# M410A.net
KiCad netlist of a schematic drawn in EAGLE
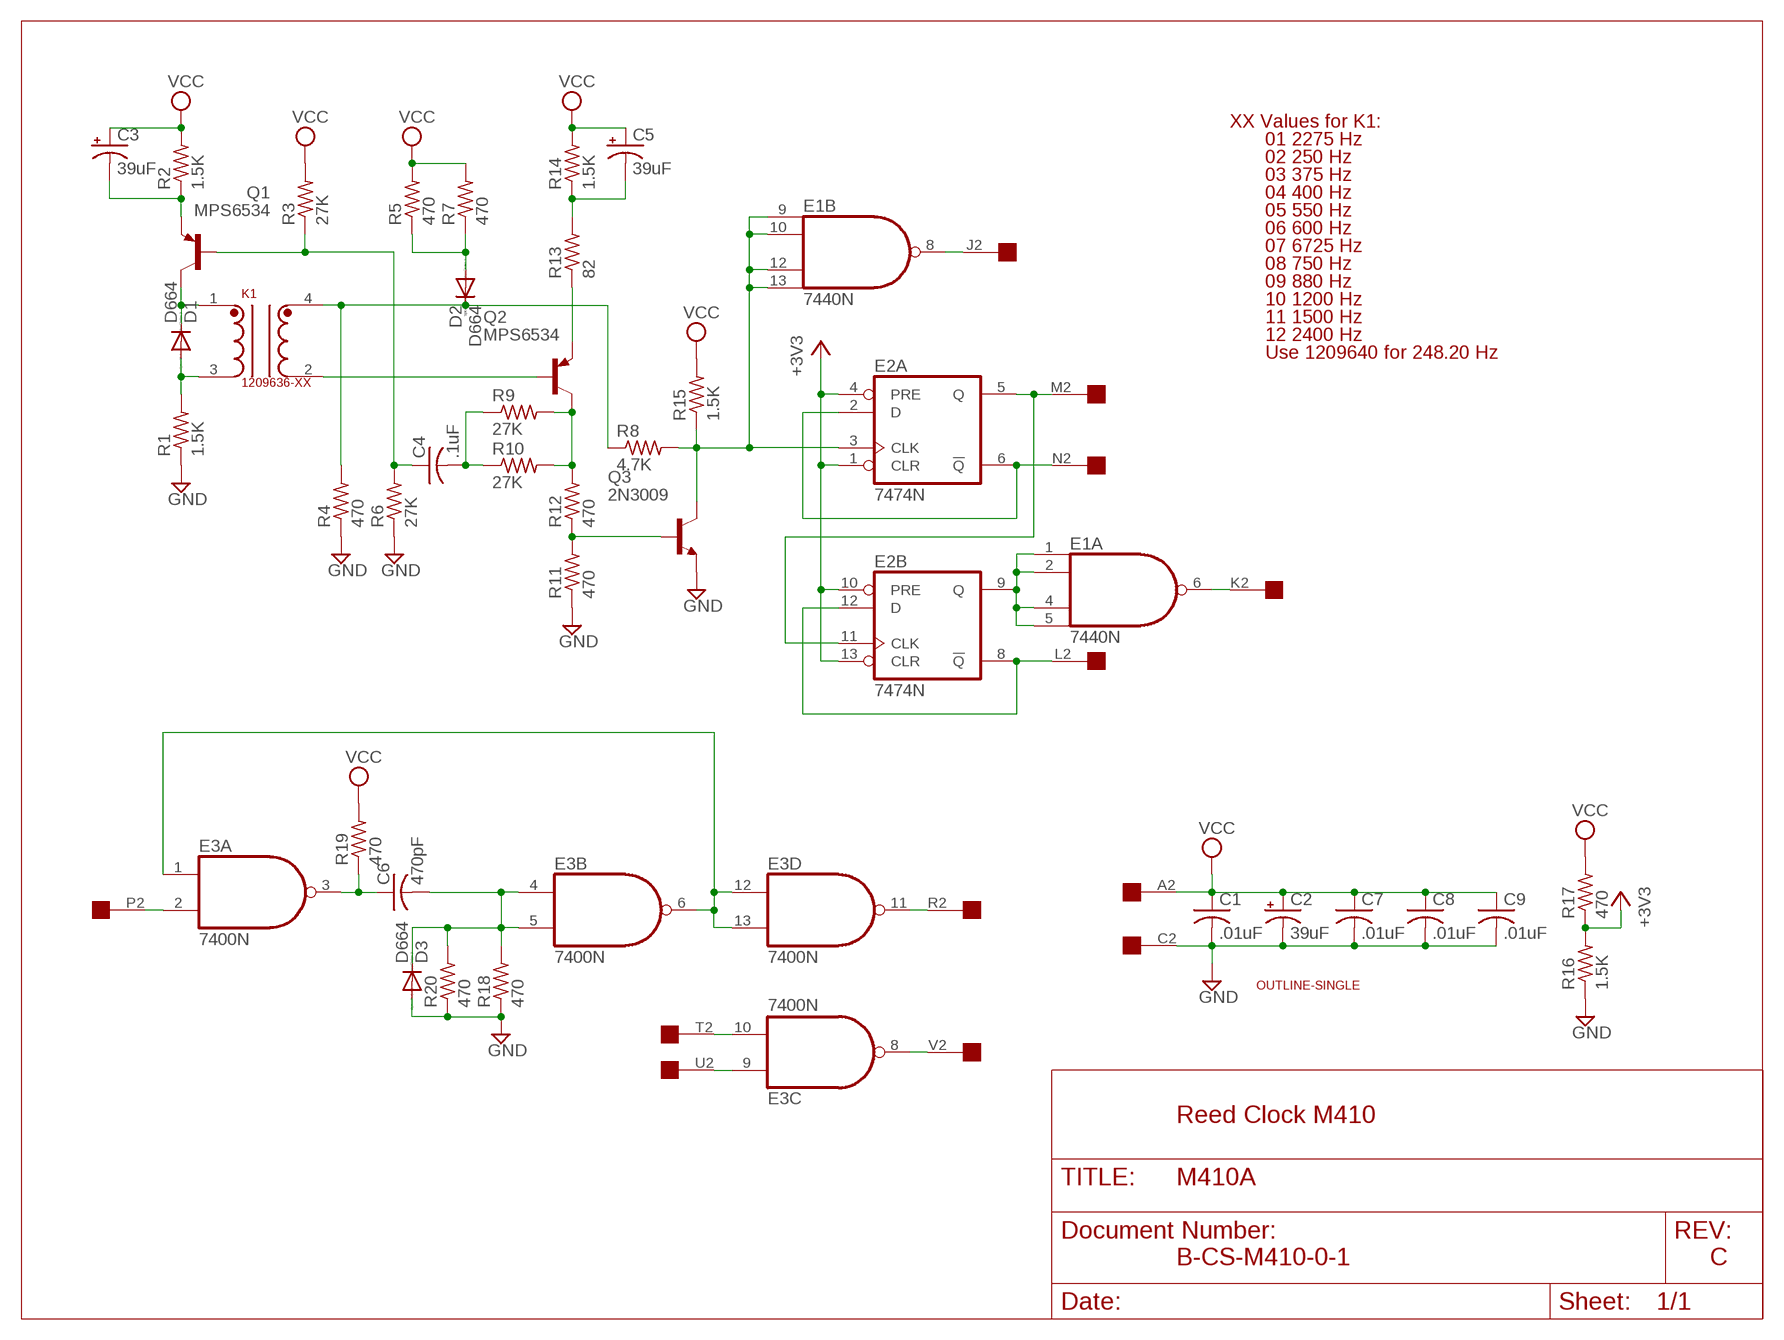
[diagram p0: schematic, sheet 1]

(export (version "E")
  (design (tool "Eeschema 10.0.6"))
  (components
    (comp (ref "C1")
      (value ".01uF")
      (footprint "eagle-import:C050-025X075")
      (libsource (lib "eagle-import") (part "C-US050-025X075"))
    )
    (comp (ref "C2")
      (value "39uF")
      (footprint "eagle-import:E12-8")
      (libsource (lib "eagle-import") (part "CPOL-USE20-8AXIAL"))
    )
    (comp (ref "C3")
      (value "39uF")
      (footprint "eagle-import:E12-8")
      (libsource (lib "eagle-import") (part "CPOL-USE20-8AXIAL"))
    )
    (comp (ref "C4")
      (value ".1uF")
      (footprint "eagle-import:C150-054X183")
      (libsource (lib "eagle-import") (part "C-US150-054X183"))
    )
    (comp (ref "C5")
      (value "39uF")
      (footprint "eagle-import:E12-8")
      (libsource (lib "eagle-import") (part "CPOL-USE20-8AXIAL"))
    )
    (comp (ref "C6")
      (value "470pF")
      (footprint "eagle-import:C075-032X103")
      (libsource (lib "eagle-import") (part "C-US075-032X103"))
    )
    (comp (ref "C7")
      (value ".01uF")
      (footprint "eagle-import:C050-025X075")
      (libsource (lib "eagle-import") (part "C-US050-025X075"))
    )
    (comp (ref "C8")
      (value ".01uF")
      (footprint "eagle-import:C050-025X075")
      (libsource (lib "eagle-import") (part "C-US050-025X075"))
    )
    (comp (ref "C9")
      (value ".01uF")
      (footprint "eagle-import:C050-025X075")
      (libsource (lib "eagle-import") (part "C-US050-025X075"))
    )
    (comp (ref "D1")
      (value "D664")
      (footprint "eagle-import:DO35-10")
      (libsource (lib "eagle-import") (part "DIODE-DO35-10"))
    )
    (comp (ref "D2")
      (value "D664")
      (footprint "eagle-import:DO35-10")
      (libsource (lib "eagle-import") (part "DIODE-DO35-10"))
    )
    (comp (ref "D3")
      (value "D664")
      (footprint "eagle-import:DO35-10")
      (libsource (lib "eagle-import") (part "DIODE-DO35-10"))
    )
    (comp (ref "E1")
      (value "7440N")
      (footprint "eagle-import:DIL14")
      (libsource (lib "eagle-import") (part "7440N"))
    )
    (comp (ref "E2")
      (value "7474N")
      (footprint "eagle-import:DIL14")
      (libsource (lib "eagle-import") (part "7474NS"))
    )
    (comp (ref "E3")
      (value "7400N")
      (footprint "eagle-import:DIL14")
      (libsource (lib "eagle-import") (part "7400N"))
    )
    (comp (ref "K1")
      (value "1209636-XX")
      (footprint "eagle-import:RESONATOR")
      (libsource (lib "eagle-import") (part "RESONATOR"))
    )
    (comp (ref "Q1")
      (value "MPS6534")
      (footprint "eagle-import:TO5")
      (libsource (lib "eagle-import") (part "-PNP-TO5"))
    )
    (comp (ref "Q2")
      (value "MPS6534")
      (footprint "eagle-import:TO5")
      (libsource (lib "eagle-import") (part "-PNP-TO5"))
    )
    (comp (ref "Q3")
      (value "2N3009")
      (footprint "eagle-import:TO5")
      (libsource (lib "eagle-import") (part "-NPN-TO5"))
    )
    (comp (ref "R1")
      (value "1.5K")
      (footprint "eagle-import:0207_10")
      (libsource (lib "eagle-import") (part "R-US_0207/10"))
    )
    (comp (ref "R2")
      (value "1.5K")
      (footprint "eagle-import:0207_10")
      (libsource (lib "eagle-import") (part "R-US_0207/10"))
    )
    (comp (ref "R3")
      (value "27K")
      (footprint "eagle-import:0207_10")
      (libsource (lib "eagle-import") (part "R-US_0207/10"))
    )
    (comp (ref "R4")
      (value "470")
      (footprint "eagle-import:0207_10")
      (libsource (lib "eagle-import") (part "R-US_0207/10"))
    )
    (comp (ref "R5")
      (value "470")
      (footprint "eagle-import:0207_10")
      (libsource (lib "eagle-import") (part "R-US_0207/10"))
    )
    (comp (ref "R6")
      (value "27K")
      (footprint "eagle-import:0207_10")
      (libsource (lib "eagle-import") (part "R-US_0207/10"))
    )
    (comp (ref "R7")
      (value "470")
      (footprint "eagle-import:0207_10")
      (libsource (lib "eagle-import") (part "R-US_0207/10"))
    )
    (comp (ref "R8")
      (value "4.7K")
      (footprint "eagle-import:0207_10")
      (libsource (lib "eagle-import") (part "R-US_0207/10"))
    )
    (comp (ref "R9")
      (value "27K")
      (footprint "eagle-import:0207_10")
      (libsource (lib "eagle-import") (part "R-US_0207/10"))
    )
    (comp (ref "R10")
      (value "27K")
      (footprint "eagle-import:0207_10")
      (libsource (lib "eagle-import") (part "R-US_0207/10"))
    )
    (comp (ref "R11")
      (value "470")
      (footprint "eagle-import:0207_10")
      (libsource (lib "eagle-import") (part "R-US_0207/10"))
    )
    (comp (ref "R12")
      (value "470")
      (footprint "eagle-import:0207_10")
      (libsource (lib "eagle-import") (part "R-US_0207/10"))
    )
    (comp (ref "R13")
      (value "82")
      (footprint "eagle-import:0207_10")
      (libsource (lib "eagle-import") (part "R-US_0207/10"))
    )
    (comp (ref "R14")
      (value "1.5K")
      (footprint "eagle-import:0207_10")
      (libsource (lib "eagle-import") (part "R-US_0207/10"))
    )
    (comp (ref "R15")
      (value "1.5K")
      (footprint "eagle-import:0207_10")
      (libsource (lib "eagle-import") (part "R-US_0207/10"))
    )
    (comp (ref "R16")
      (value "1.5K")
      (footprint "eagle-import:0207_10")
      (libsource (lib "eagle-import") (part "R-US_0207/10"))
    )
    (comp (ref "R17")
      (value "470")
      (footprint "eagle-import:0207_10")
      (libsource (lib "eagle-import") (part "R-US_0207/10"))
    )
    (comp (ref "R18")
      (value "470")
      (footprint "eagle-import:0207_10")
      (libsource (lib "eagle-import") (part "R-US_0207/10"))
    )
    (comp (ref "R19")
      (value "470")
      (footprint "eagle-import:0207_10")
      (libsource (lib "eagle-import") (part "R-US_0207/10"))
    )
    (comp (ref "R20")
      (value "470")
      (footprint "eagle-import:0207_10")
      (libsource (lib "eagle-import") (part "R-US_0207/10"))
    )
    (comp (ref "U$1")
      (value "OUTLINE-SINGLE")
      (footprint "eagle-import:SINGLE")
      (libsource (lib "eagle-import") (part "OUTLINE-SINGLE"))
    )
    (comp (ref "U$3")
      (value "EDGE-1")
      (footprint "eagle-import:EDGE-CON1")
      (libsource (lib "eagle-import") (part "EDGE-1"))
    )
  )
  (nets
    (net (code "1") (name "+3V3") (class "Default")
      (node (ref "E2") (pin "1") (pinfunction "CLR_1") (pintype "input"))
      (node (ref "E2") (pin "10") (pinfunction "PRE_10") (pintype "input"))
      (node (ref "E2") (pin "13") (pinfunction "CLR_13") (pintype "input"))
      (node (ref "E2") (pin "4") (pinfunction "PRE_4") (pintype "input"))
      (node (ref "R16") (pin "2") (pinfunction "2_2") (pintype "passive"))
      (node (ref "R17") (pin "1") (pinfunction "1_1") (pintype "passive"))
    )
    (net (code "2") (name "GND") (class "Default")
      (node (ref "C1") (pin "2") (pinfunction "2_2") (pintype "passive"))
      (node (ref "C2") (pin "-") (pinfunction "-_-") (pintype "passive"))
      (node (ref "C7") (pin "2") (pinfunction "2_2") (pintype "passive"))
      (node (ref "C8") (pin "2") (pinfunction "2_2") (pintype "passive"))
      (node (ref "C9") (pin "2") (pinfunction "2_2") (pintype "passive"))
      (node (ref "D3") (pin "A") (pinfunction "A_A") (pintype "passive"))
      (node (ref "Q3") (pin "1") (pinfunction "E_1") (pintype "passive"))
      (node (ref "R1") (pin "1") (pinfunction "1_1") (pintype "passive"))
      (node (ref "R11") (pin "1") (pinfunction "1_1") (pintype "passive"))
      (node (ref "R16") (pin "1") (pinfunction "1_1") (pintype "passive"))
      (node (ref "R18") (pin "1") (pinfunction "1_1") (pintype "passive"))
      (node (ref "R20") (pin "1") (pinfunction "1_1") (pintype "passive"))
      (node (ref "R4") (pin "1") (pinfunction "1_1") (pintype "passive"))
      (node (ref "R6") (pin "1") (pinfunction "1_1") (pintype "passive"))
      (node (ref "U$3") (pin "C2") (pinfunction "1_C2") (pintype "bidirectional"))
    )
    (net (code "3") (name "Net-(C4-Pad2)") (class "Default")
      (node (ref "C4") (pin "2") (pinfunction "2_2") (pintype "passive"))
      (node (ref "R10") (pin "1") (pinfunction "1_1") (pintype "passive"))
      (node (ref "R9") (pin "1") (pinfunction "1_1") (pintype "passive"))
    )
    (net (code "4") (name "Net-(C5-Pad-)") (class "Default")
      (node (ref "C5") (pin "-") (pinfunction "-_-") (pintype "passive"))
      (node (ref "R13") (pin "2") (pinfunction "2_2") (pintype "passive"))
      (node (ref "R14") (pin "1") (pinfunction "1_1") (pintype "passive"))
    )
    (net (code "5") (name "Net-(D2-PadA)") (class "Default")
      (node (ref "D2") (pin "A") (pinfunction "A_A") (pintype "passive"))
      (node (ref "R5") (pin "1") (pinfunction "1_1") (pintype "passive"))
      (node (ref "R7") (pin "1") (pinfunction "1_1") (pintype "passive"))
    )
    (net (code "6") (name "Net-(E1C-I0)") (class "Default")
      (node (ref "E1") (pin "1") (pinfunction "I0_1") (pintype "input"))
      (node (ref "E1") (pin "2") (pinfunction "I1_2") (pintype "input"))
      (node (ref "E1") (pin "4") (pinfunction "I2_4") (pintype "input"))
      (node (ref "E1") (pin "5") (pinfunction "I3_5") (pintype "input"))
      (node (ref "E2") (pin "9") (pinfunction "Q_9") (pintype "output"))
    )
    (net (code "7") (name "Net-(E1C-O)") (class "Default")
      (node (ref "E1") (pin "6") (pinfunction "O_6") (pintype "output"))
      (node (ref "U$3") (pin "K2") (pinfunction "1_K2") (pintype "bidirectional"))
    )
    (net (code "8") (name "Net-(E1D-I0)") (class "Default")
      (node (ref "E1") (pin "10") (pinfunction "I1_10") (pintype "input"))
      (node (ref "E1") (pin "12") (pinfunction "I2_12") (pintype "input"))
      (node (ref "E1") (pin "13") (pinfunction "I3_13") (pintype "input"))
      (node (ref "E1") (pin "9") (pinfunction "I0_9") (pintype "input"))
      (node (ref "E2") (pin "3") (pinfunction "CLK_3") (pintype "input"))
      (node (ref "Q3") (pin "3") (pinfunction "C_3") (pintype "passive"))
      (node (ref "R15") (pin "1") (pinfunction "1_1") (pintype "passive"))
      (node (ref "R8") (pin "2") (pinfunction "2_2") (pintype "passive"))
    )
    (net (code "9") (name "Net-(E1D-O)") (class "Default")
      (node (ref "E1") (pin "8") (pinfunction "O_8") (pintype "output"))
      (node (ref "U$3") (pin "J2") (pinfunction "1_J2") (pintype "bidirectional"))
    )
    (net (code "10") (name "Net-(E2A-D)") (class "Default")
      (node (ref "E2") (pin "2") (pinfunction "D_2") (pintype "input"))
      (node (ref "E2") (pin "6") (pinfunction "~{Q}_6") (pintype "output"))
      (node (ref "U$3") (pin "N2") (pinfunction "1_N2") (pintype "bidirectional"))
    )
    (net (code "11") (name "Net-(E2A-Q)") (class "Default")
      (node (ref "E2") (pin "11") (pinfunction "CLK_11") (pintype "input"))
      (node (ref "E2") (pin "5") (pinfunction "Q_5") (pintype "output"))
      (node (ref "U$3") (pin "M2") (pinfunction "1_M2") (pintype "bidirectional"))
    )
    (net (code "12") (name "Net-(E2B-D)") (class "Default")
      (node (ref "E2") (pin "12") (pinfunction "D_12") (pintype "input"))
      (node (ref "E2") (pin "8") (pinfunction "~{Q}_8") (pintype "output"))
      (node (ref "U$3") (pin "L2") (pinfunction "1_L2") (pintype "bidirectional"))
    )
    (net (code "13") (name "Net-(E3A-I0)") (class "Default")
      (node (ref "E3") (pin "1") (pinfunction "I0_1") (pintype "input"))
      (node (ref "E3") (pin "12") (pinfunction "I0_12") (pintype "input"))
      (node (ref "E3") (pin "13") (pinfunction "I1_13") (pintype "input"))
      (node (ref "E3") (pin "6") (pinfunction "O_6") (pintype "output"))
    )
    (net (code "14") (name "Net-(E3A-I1)") (class "Default")
      (node (ref "E3") (pin "2") (pinfunction "I1_2") (pintype "input"))
      (node (ref "U$3") (pin "P2") (pinfunction "1_P2") (pintype "bidirectional"))
    )
    (net (code "15") (name "Net-(E3A-O)") (class "Default")
      (node (ref "C6") (pin "1") (pinfunction "1_1") (pintype "passive"))
      (node (ref "E3") (pin "3") (pinfunction "O_3") (pintype "output"))
      (node (ref "R19") (pin "1") (pinfunction "1_1") (pintype "passive"))
    )
    (net (code "16") (name "Net-(E3B-I0)") (class "Default")
      (node (ref "C6") (pin "2") (pinfunction "2_2") (pintype "passive"))
      (node (ref "D3") (pin "C") (pinfunction "C_C") (pintype "passive"))
      (node (ref "E3") (pin "4") (pinfunction "I0_4") (pintype "input"))
      (node (ref "E3") (pin "5") (pinfunction "I1_5") (pintype "input"))
      (node (ref "R18") (pin "2") (pinfunction "2_2") (pintype "passive"))
      (node (ref "R20") (pin "2") (pinfunction "2_2") (pintype "passive"))
    )
    (net (code "17") (name "Net-(E3C-I0)") (class "Default")
      (node (ref "E3") (pin "9") (pinfunction "I0_9") (pintype "input"))
      (node (ref "U$3") (pin "U2") (pinfunction "1_U2") (pintype "bidirectional"))
    )
    (net (code "18") (name "Net-(E3C-I1)") (class "Default")
      (node (ref "E3") (pin "10") (pinfunction "I1_10") (pintype "input"))
      (node (ref "U$3") (pin "T2") (pinfunction "1_T2") (pintype "bidirectional"))
    )
    (net (code "19") (name "Net-(E3C-O)") (class "Default")
      (node (ref "E3") (pin "8") (pinfunction "O_8") (pintype "output"))
      (node (ref "U$3") (pin "V2") (pinfunction "1_V2") (pintype "bidirectional"))
    )
    (net (code "20") (name "Net-(E3D-O)") (class "Default")
      (node (ref "E3") (pin "11") (pinfunction "O_11") (pintype "output"))
      (node (ref "U$3") (pin "R2") (pinfunction "1_R2") (pintype "bidirectional"))
    )
    (net (code "21") (name "Net-(K1-P$2)") (class "Default")
      (node (ref "D1") (pin "C") (pinfunction "C_C") (pintype "passive"))
      (node (ref "K1") (pin "1") (pinfunction "P$2_1") (pintype "passive"))
      (node (ref "Q1") (pin "3") (pinfunction "C_3") (pintype "passive"))
    )
    (net (code "22") (name "Net-(K1-P$4)") (class "Default")
      (node (ref "D2") (pin "C") (pinfunction "C_C") (pintype "passive"))
      (node (ref "K1") (pin "4") (pinfunction "P$4_4") (pintype "passive"))
      (node (ref "R4") (pin "2") (pinfunction "2_2") (pintype "passive"))
      (node (ref "R8") (pin "1") (pinfunction "1_1") (pintype "passive"))
    )
    (net (code "23") (name "Net-(K1-P$5)") (class "Default")
      (node (ref "K1") (pin "2") (pinfunction "P$5_2") (pintype "passive"))
      (node (ref "Q2") (pin "2") (pinfunction "B_2") (pintype "passive"))
    )
    (net (code "24") (name "Net-(K1-P$7)") (class "Default")
      (node (ref "D1") (pin "A") (pinfunction "A_A") (pintype "passive"))
      (node (ref "K1") (pin "3") (pinfunction "P$7_3") (pintype "passive"))
      (node (ref "R1") (pin "2") (pinfunction "2_2") (pintype "passive"))
    )
    (net (code "25") (name "Net-(Q1-B)") (class "Default")
      (node (ref "C4") (pin "1") (pinfunction "1_1") (pintype "passive"))
      (node (ref "Q1") (pin "2") (pinfunction "B_2") (pintype "passive"))
      (node (ref "R3") (pin "1") (pinfunction "1_1") (pintype "passive"))
      (node (ref "R6") (pin "2") (pinfunction "2_2") (pintype "passive"))
    )
    (net (code "26") (name "Net-(Q1-E)") (class "Default")
      (node (ref "C3") (pin "-") (pinfunction "-_-") (pintype "passive"))
      (node (ref "Q1") (pin "1") (pinfunction "E_1") (pintype "passive"))
      (node (ref "R2") (pin "1") (pinfunction "1_1") (pintype "passive"))
    )
    (net (code "27") (name "Net-(Q2-C)") (class "Default")
      (node (ref "Q2") (pin "3") (pinfunction "C_3") (pintype "passive"))
      (node (ref "R10") (pin "2") (pinfunction "2_2") (pintype "passive"))
      (node (ref "R12") (pin "2") (pinfunction "2_2") (pintype "passive"))
      (node (ref "R9") (pin "2") (pinfunction "2_2") (pintype "passive"))
    )
    (net (code "28") (name "Net-(Q2-E)") (class "Default")
      (node (ref "Q2") (pin "1") (pinfunction "E_1") (pintype "passive"))
      (node (ref "R13") (pin "1") (pinfunction "1_1") (pintype "passive"))
    )
    (net (code "29") (name "Net-(Q3-B)") (class "Default")
      (node (ref "Q3") (pin "2") (pinfunction "B_2") (pintype "passive"))
      (node (ref "R11") (pin "2") (pinfunction "2_2") (pintype "passive"))
      (node (ref "R12") (pin "1") (pinfunction "1_1") (pintype "passive"))
    )
    (net (code "30") (name "VCC") (class "Default")
      (node (ref "C1") (pin "1") (pinfunction "1_1") (pintype "passive"))
      (node (ref "C2") (pin "+") (pinfunction "+_+") (pintype "passive"))
      (node (ref "C3") (pin "+") (pinfunction "+_+") (pintype "passive"))
      (node (ref "C5") (pin "+") (pinfunction "+_+") (pintype "passive"))
      (node (ref "C7") (pin "1") (pinfunction "1_1") (pintype "passive"))
      (node (ref "C8") (pin "1") (pinfunction "1_1") (pintype "passive"))
      (node (ref "C9") (pin "1") (pinfunction "1_1") (pintype "passive"))
      (node (ref "R14") (pin "2") (pinfunction "2_2") (pintype "passive"))
      (node (ref "R15") (pin "2") (pinfunction "2_2") (pintype "passive"))
      (node (ref "R17") (pin "2") (pinfunction "2_2") (pintype "passive"))
      (node (ref "R19") (pin "2") (pinfunction "2_2") (pintype "passive"))
      (node (ref "R2") (pin "2") (pinfunction "2_2") (pintype "passive"))
      (node (ref "R3") (pin "2") (pinfunction "2_2") (pintype "passive"))
      (node (ref "R5") (pin "2") (pinfunction "2_2") (pintype "passive"))
      (node (ref "R7") (pin "2") (pinfunction "2_2") (pintype "passive"))
      (node (ref "U$3") (pin "A2") (pinfunction "1_A2") (pintype "bidirectional"))
    )
  )
)
